# ProPrj_TPS__2025-07-25.net
KiCad netlist of a schematic drawn in EasyEDA Pro
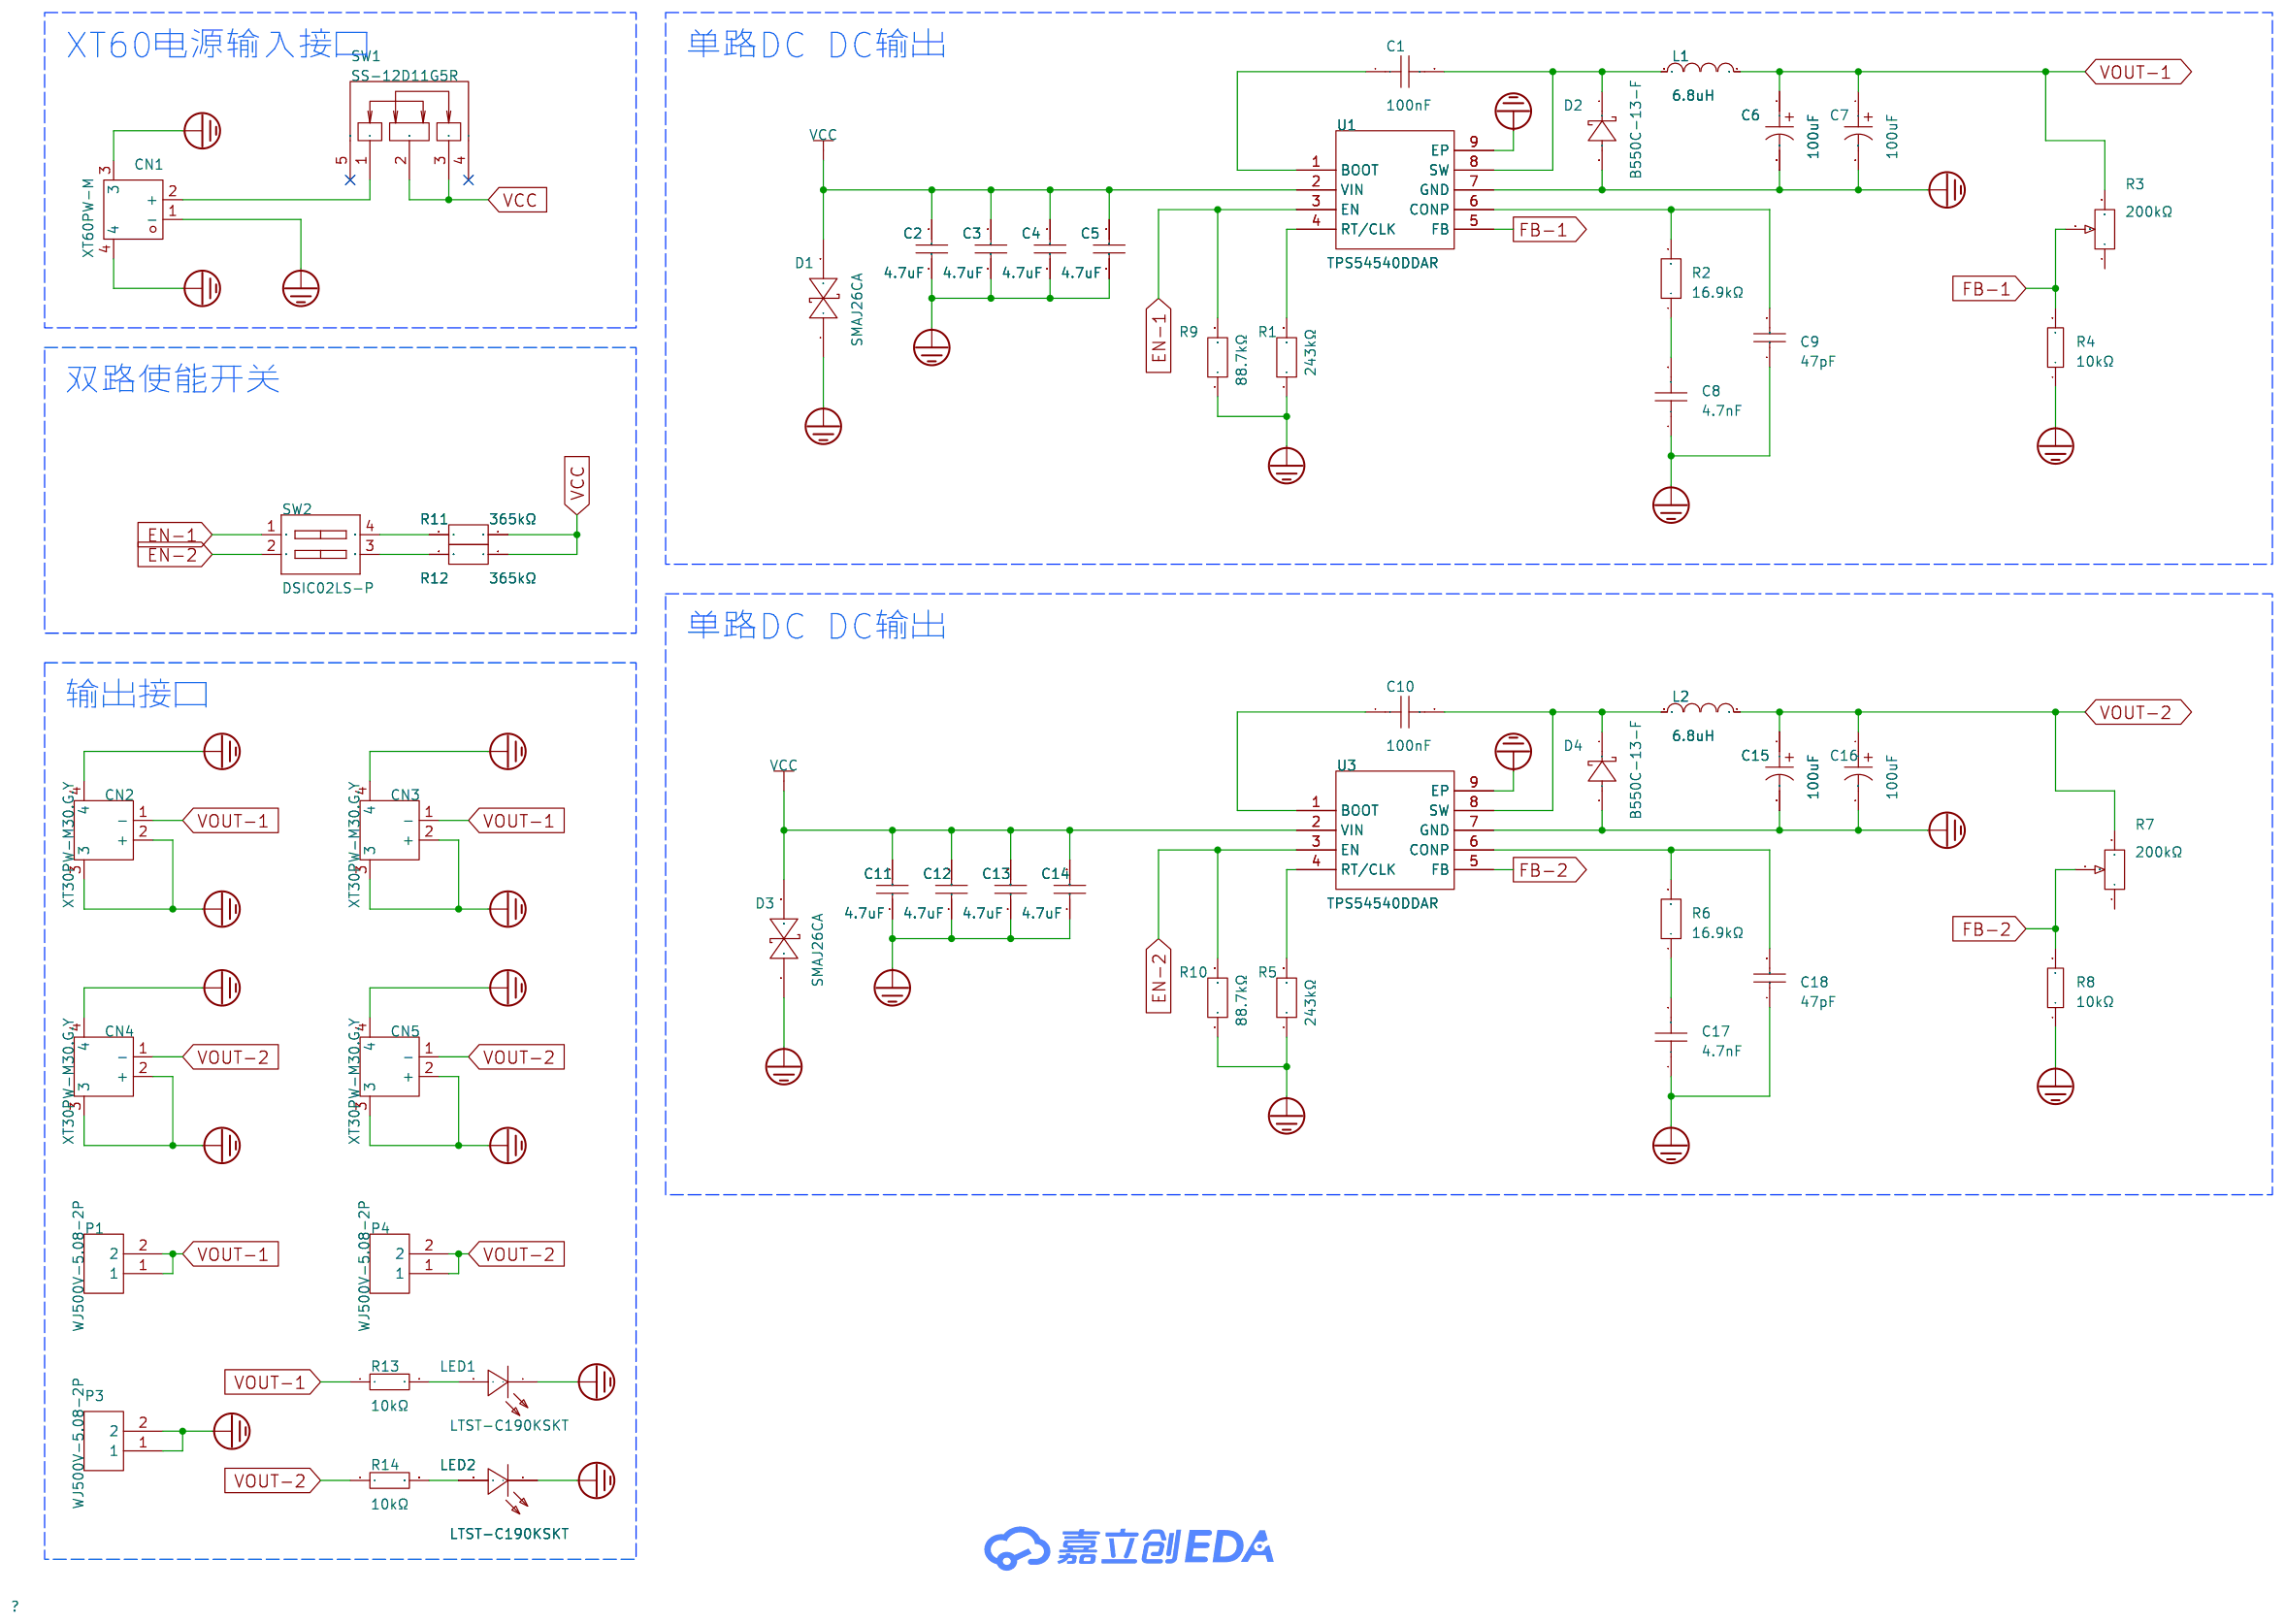
[diagram p0: schematic sheet]

(export (version "E")
  (design (tool "Eeschema 10.0.6"))
  (components
    (comp (ref "C1")
      (value "100nF")
      (footprint "easyedapro:C0603")
      (description "容值:100nF;精度:±10%;额定电压:50V;温度系数:X7R;")
      (fields
        (field (name "Manufacturer Part") "CGA0603X7R104K500JT")
        (field (name "Manufacturer") "HRE(芯声)")
      )
      (libsource (lib "easyedapro") (part "CGA0603X7R104K500JT"))
    )
    (comp (ref "C2")
      (value "4.7uF")
      (footprint "easyedapro:C0805")
      (description "容值:4.7uF;精度:±10%;额定电压:50V;材质(温度系数):X5R;")
      (fields
        (field (name "Manufacturer Part") "CL21A475KBQNNNE")
        (field (name "Manufacturer") "SAMSUNG(三星)")
      )
      (libsource (lib "easyedapro") (part "CL21A475KBQNNNE"))
    )
    (comp (ref "C3")
      (value "4.7uF")
      (footprint "easyedapro:C0805")
      (description "容值:4.7uF;精度:±10%;额定电压:50V;材质(温度系数):X5R;")
      (fields
        (field (name "Manufacturer Part") "CL21A475KBQNNNE")
        (field (name "Manufacturer") "SAMSUNG(三星)")
      )
      (libsource (lib "easyedapro") (part "CL21A475KBQNNNE"))
    )
    (comp (ref "C4")
      (value "4.7uF")
      (footprint "easyedapro:C0805")
      (description "容值:4.7uF;精度:±10%;额定电压:50V;材质(温度系数):X5R;")
      (fields
        (field (name "Manufacturer Part") "CL21A475KBQNNNE")
        (field (name "Manufacturer") "SAMSUNG(三星)")
      )
      (libsource (lib "easyedapro") (part "CL21A475KBQNNNE"))
    )
    (comp (ref "C5")
      (value "4.7uF")
      (footprint "easyedapro:C0805")
      (description "容值:4.7uF;精度:±10%;额定电压:50V;材质(温度系数):X5R;")
      (fields
        (field (name "Manufacturer Part") "CL21A475KBQNNNE")
        (field (name "Manufacturer") "SAMSUNG(三星)")
      )
      (libsource (lib "easyedapro") (part "CL21A475KBQNNNE"))
    )
    (comp (ref "C6")
      (value "100uF")
      (footprint "easyedapro:CAP-TH_BD8.0-P3.50-D0.6-FD")
      (description "容值:100uF;精度:±20%;额定电压:50V;纹波电流:2.9A@100kHz;等效串联电阻(ESR):30mΩ@100kHz;类型:聚合物;")
      (fields (field (name "Manufacturer Part") "PA50V100M8x8") (field (name "Manufacturer") "捷而瑞"))
      (libsource (lib "easyedapro") (part "PA50V100M8X8"))
    )
    (comp (ref "C7")
      (value "100uF")
      (footprint "easyedapro:CAP-TH_BD8.0-P3.50-D0.6-FD")
      (description "容值:100uF;精度:±20%;额定电压:50V;纹波电流:2.9A@100kHz;等效串联电阻(ESR):30mΩ@100kHz;类型:聚合物;")
      (fields (field (name "Manufacturer Part") "PA50V100M8x8") (field (name "Manufacturer") "捷而瑞"))
      (libsource (lib "easyedapro") (part "PA50V100M8X8"))
    )
    (comp (ref "C8")
      (value "4.7nF")
      (footprint "easyedapro:C0603")
      (description "容值:4.7nF;精度:±10%;额定电压:50V;温度系数:X7R;")
      (fields
        (field (name "Manufacturer Part") "CGA0603X7R472K500JT")
        (field (name "Manufacturer") "HRE(芯声)")
      )
      (libsource (lib "easyedapro") (part "CGA0603X7R472K500JT"))
    )
    (comp (ref "C9")
      (value "47pF")
      (footprint "easyedapro:C0603")
      (description "容值:47pF;精度:±5%;额定电压:50V;材质(温度系数):C0G;")
      (fields
        (field (name "Manufacturer Part") "CL10C470JB8NNNC")
        (field (name "Manufacturer") "SAMSUNG(三星)")
      )
      (libsource (lib "easyedapro") (part "CL10C470JB8NNNC"))
    )
    (comp (ref "C10")
      (value "100nF")
      (footprint "easyedapro:C0603")
      (description "容值:100nF;精度:±10%;额定电压:50V;温度系数:X7R;")
      (fields
        (field (name "Manufacturer Part") "CGA0603X7R104K500JT")
        (field (name "Manufacturer") "HRE(芯声)")
      )
      (libsource (lib "easyedapro") (part "CGA0603X7R104K500JT"))
    )
    (comp (ref "C11")
      (value "4.7uF")
      (footprint "easyedapro:C0805")
      (description "容值:4.7uF;精度:±10%;额定电压:50V;材质(温度系数):X5R;")
      (fields
        (field (name "Manufacturer Part") "CL21A475KBQNNNE")
        (field (name "Manufacturer") "SAMSUNG(三星)")
      )
      (libsource (lib "easyedapro") (part "CL21A475KBQNNNE"))
    )
    (comp (ref "C12")
      (value "4.7uF")
      (footprint "easyedapro:C0805")
      (description "容值:4.7uF;精度:±10%;额定电压:50V;材质(温度系数):X5R;")
      (fields
        (field (name "Manufacturer Part") "CL21A475KBQNNNE")
        (field (name "Manufacturer") "SAMSUNG(三星)")
      )
      (libsource (lib "easyedapro") (part "CL21A475KBQNNNE"))
    )
    (comp (ref "C13")
      (value "4.7uF")
      (footprint "easyedapro:C0805")
      (description "容值:4.7uF;精度:±10%;额定电压:50V;材质(温度系数):X5R;")
      (fields
        (field (name "Manufacturer Part") "CL21A475KBQNNNE")
        (field (name "Manufacturer") "SAMSUNG(三星)")
      )
      (libsource (lib "easyedapro") (part "CL21A475KBQNNNE"))
    )
    (comp (ref "C14")
      (value "4.7uF")
      (footprint "easyedapro:C0805")
      (description "容值:4.7uF;精度:±10%;额定电压:50V;材质(温度系数):X5R;")
      (fields
        (field (name "Manufacturer Part") "CL21A475KBQNNNE")
        (field (name "Manufacturer") "SAMSUNG(三星)")
      )
      (libsource (lib "easyedapro") (part "CL21A475KBQNNNE"))
    )
    (comp (ref "C15")
      (value "100uF")
      (footprint "easyedapro:CAP-TH_BD8.0-P3.50-D0.6-FD")
      (description "容值:100uF;精度:±20%;额定电压:50V;纹波电流:2.9A@100kHz;等效串联电阻(ESR):30mΩ@100kHz;类型:聚合物;")
      (fields (field (name "Manufacturer Part") "PA50V100M8x8") (field (name "Manufacturer") "捷而瑞"))
      (libsource (lib "easyedapro") (part "PA50V100M8X8"))
    )
    (comp (ref "C16")
      (value "100uF")
      (footprint "easyedapro:CAP-TH_BD8.0-P3.50-D0.6-FD")
      (description "容值:100uF;精度:±20%;额定电压:50V;纹波电流:2.9A@100kHz;等效串联电阻(ESR):30mΩ@100kHz;类型:聚合物;")
      (fields (field (name "Manufacturer Part") "PA50V100M8x8") (field (name "Manufacturer") "捷而瑞"))
      (libsource (lib "easyedapro") (part "PA50V100M8X8"))
    )
    (comp (ref "C17")
      (value "4.7nF")
      (footprint "easyedapro:C0603")
      (description "容值:4.7nF;精度:±10%;额定电压:50V;温度系数:X7R;")
      (fields
        (field (name "Manufacturer Part") "CGA0603X7R472K500JT")
        (field (name "Manufacturer") "HRE(芯声)")
      )
      (libsource (lib "easyedapro") (part "CGA0603X7R472K500JT"))
    )
    (comp (ref "C18")
      (value "47pF")
      (footprint "easyedapro:C0603")
      (description "容值:47pF;精度:±5%;额定电压:50V;材质(温度系数):C0G;")
      (fields
        (field (name "Manufacturer Part") "CL10C470JB8NNNC")
        (field (name "Manufacturer") "SAMSUNG(三星)")
      )
      (libsource (lib "easyedapro") (part "CL10C470JB8NNNC"))
    )
    (comp (ref "CN1")
      (value "XT60PW-M")
      (footprint "easyedapro:CONN-TH_XT60PW-M")
      (description "类别:-;类型1:-;")
      (fields (field (name "Manufacturer") "AMASS(艾迈斯)"))
      (libsource (lib "easyedapro") (part "XT60PW-M"))
    )
    (comp (ref "CN2")
      (value "XT30PW-M30.G.Y")
      (footprint "easyedapro:CONN-TH_XT30PW-M")
      (description "类别:-;类型1:-;")
      (fields (field (name "Manufacturer") "AMASS(艾迈斯)"))
      (libsource (lib "easyedapro") (part "XT30PW-M"))
    )
    (comp (ref "CN3")
      (value "XT30PW-M30.G.Y")
      (footprint "easyedapro:CONN-TH_XT30PW-M")
      (description "类别:-;类型1:-;")
      (fields (field (name "Manufacturer") "AMASS(艾迈斯)"))
      (libsource (lib "easyedapro") (part "XT30PW-M"))
    )
    (comp (ref "CN4")
      (value "XT30PW-M30.G.Y")
      (footprint "easyedapro:CONN-TH_XT30PW-M")
      (description "类别:-;类型1:-;")
      (fields (field (name "Manufacturer") "AMASS(艾迈斯)"))
      (libsource (lib "easyedapro") (part "XT30PW-M"))
    )
    (comp (ref "CN5")
      (value "XT30PW-M30.G.Y")
      (footprint "easyedapro:CONN-TH_XT30PW-M")
      (description "类别:-;类型1:-;")
      (fields (field (name "Manufacturer") "AMASS(艾迈斯)"))
      (libsource (lib "easyedapro") (part "XT30PW-M"))
    )
    (comp (ref "D1")
      (value "SMAJ26CA")
      (footprint "easyedapro:SMA_L4.4-W2.6-LS5.0-BI")
      (description "反向截止电压(Vrwm):26V;最大钳位电压:42.1V;峰值脉冲电流(Ipp)@10/1000us:9.5A;击穿电压:28.9V;")
      (fields (field (name "Manufacturer") "MDD"))
      (libsource (lib "easyedapro") (part "SMAJ26CA_C173517"))
    )
    (comp (ref "D2")
      (value "B550C-13-F")
      (footprint "easyedapro:SMC_L6.9-W5.9-LS7.9-RD")
      (description "二极管配置:-;正向压降(Vf):575mV@5A;直流反向耐压(Vr):50V;整流电流:5A;")
      (fields (field (name "Manufacturer") "DIODES(美台)"))
      (libsource (lib "easyedapro") (part "B550C-13-F"))
    )
    (comp (ref "D3")
      (value "SMAJ26CA")
      (footprint "easyedapro:SMA_L4.4-W2.6-LS5.0-BI")
      (description "反向截止电压(Vrwm):26V;最大钳位电压:42.1V;峰值脉冲电流(Ipp)@10/1000us:9.5A;击穿电压:28.9V;")
      (fields (field (name "Manufacturer") "MDD"))
      (libsource (lib "easyedapro") (part "SMAJ26CA_C173517"))
    )
    (comp (ref "D4")
      (value "B550C-13-F")
      (footprint "easyedapro:SMC_L6.9-W5.9-LS7.9-RD")
      (description "二极管配置:-;正向压降(Vf):575mV@5A;直流反向耐压(Vr):50V;整流电流:5A;")
      (fields (field (name "Manufacturer") "DIODES(美台)"))
      (libsource (lib "easyedapro") (part "B550C-13-F"))
    )
    (comp (ref "L1")
      (value "6.8uH")
      (footprint "easyedapro:IND-SMD_L7.0-W6.6")
      (description "电感值:6.8uH;精度:±20%;额定电流:5A;饱和电流(Isat):6A;类型:一体成型电感;")
      (fields (field (name "Manufacturer Part") "FXL0630-6R8-M") (field (name "Manufacturer") "cjiang(长江微电)"))
      (libsource (lib "easyedapro") (part "FXL0630-6R8-M"))
    )
    (comp (ref "L2")
      (value "6.8uH")
      (footprint "easyedapro:IND-SMD_L7.0-W6.6")
      (description "电感值:6.8uH;精度:±20%;额定电流:5A;饱和电流(Isat):6A;类型:一体成型电感;")
      (fields (field (name "Manufacturer Part") "FXL0630-6R8-M") (field (name "Manufacturer") "cjiang(长江微电)"))
      (libsource (lib "easyedapro") (part "FXL0630-6R8-M"))
    )
    (comp (ref "LED1")
      (value "LTST-C190KSKT")
      (footprint "easyedapro:LED0603-RD")
      (fields (field (name "Manufacturer") "LITEON(光宝)"))
      (libsource (lib "easyedapro") (part "LTST-C190KSKT"))
    )
    (comp (ref "LED2")
      (value "LTST-C190KSKT")
      (footprint "easyedapro:LED0603-RD")
      (fields (field (name "Manufacturer") "LITEON(光宝)"))
      (libsource (lib "easyedapro") (part "LTST-C190KSKT"))
    )
    (comp (ref "P1")
      (value "WJ500V-5.08-2P")
      (footprint "easyedapro:CONN-TH_2P-P5.00_WJ500V-5.08-2P")
      (fields (field (name "Manufacturer") "KANGNEX(康奈克斯电气)"))
      (libsource (lib "easyedapro") (part "WJ500V-5.08-2P-14-00A"))
    )
    (comp (ref "P3")
      (value "WJ500V-5.08-2P")
      (footprint "easyedapro:CONN-TH_2P-P5.00_WJ500V-5.08-2P")
      (fields (field (name "Manufacturer") "KANGNEX(康奈克斯电气)"))
      (libsource (lib "easyedapro") (part "WJ500V-5.08-2P-14-00A"))
    )
    (comp (ref "P4")
      (value "WJ500V-5.08-2P")
      (footprint "easyedapro:CONN-TH_2P-P5.00_WJ500V-5.08-2P")
      (fields (field (name "Manufacturer") "KANGNEX(康奈克斯电气)"))
      (libsource (lib "easyedapro") (part "WJ500V-5.08-2P-14-00A"))
    )
    (comp (ref "R1")
      (value "243kΩ")
      (footprint "easyedapro:R0603")
      (description "电阻类型:薄膜电阻;阻值:243kΩ;精度:±0.1%;功率:100mW;温度系数:±25ppm/°C;")
      (fields (field (name "Manufacturer Part") "RT0603BRD07243KL") (field (name "Manufacturer") "YAGEO(国巨)"))
      (libsource (lib "easyedapro") (part "RT0603BRD07243KL"))
    )
    (comp (ref "R2")
      (value "16.9kΩ")
      (footprint "easyedapro:R0603")
      (description "电阻类型:薄膜电阻;阻值:16.9kΩ;精度:±0.1%;功率:100mW;温度系数:±25ppm/°C;")
      (fields (field (name "Manufacturer Part") "RT0603BRD0716K9L") (field (name "Manufacturer") "YAGEO(国巨)"))
      (libsource (lib "easyedapro") (part "RT0603BRD0716K9L"))
    )
    (comp (ref "R3")
      (value "200kΩ")
      (footprint "easyedapro:RES-ADJ-TH_3P-L7.1-W6.9-P2.50-L_3362P")
      (description "阻值:200kΩ;精度:±10%;")
      (fields (field (name "Manufacturer Part") "3362P-1-204") (field (name "Manufacturer") "BOCHEN(博晨)"))
      (libsource (lib "easyedapro") (part "3362P-1-204"))
    )
    (comp (ref "R4")
      (value "10kΩ")
      (footprint "easyedapro:R0603")
      (description "电阻类型:厚膜电阻;阻值:10kΩ;精度:±1%;功率:100mW;工作电压:75V;温度系数:±100ppm/°C;")
      (fields
        (field (name "Manufacturer Part") "0603WAF1002T5E")
        (field (name "Manufacturer") "UNI-ROYAL(厚声)")
      )
      (libsource (lib "easyedapro") (part "0603WAF1002T5E"))
    )
    (comp (ref "R5")
      (value "243kΩ")
      (footprint "easyedapro:R0603")
      (description "电阻类型:薄膜电阻;阻值:243kΩ;精度:±0.1%;功率:100mW;温度系数:±25ppm/°C;")
      (fields (field (name "Manufacturer Part") "RT0603BRD07243KL") (field (name "Manufacturer") "YAGEO(国巨)"))
      (libsource (lib "easyedapro") (part "RT0603BRD07243KL"))
    )
    (comp (ref "R6")
      (value "16.9kΩ")
      (footprint "easyedapro:R0603")
      (description "电阻类型:薄膜电阻;阻值:16.9kΩ;精度:±0.1%;功率:100mW;温度系数:±25ppm/°C;")
      (fields (field (name "Manufacturer Part") "RT0603BRD0716K9L") (field (name "Manufacturer") "YAGEO(国巨)"))
      (libsource (lib "easyedapro") (part "RT0603BRD0716K9L"))
    )
    (comp (ref "R7")
      (value "200kΩ")
      (footprint "easyedapro:RES-ADJ-TH_3P-L7.1-W6.9-P2.50-L_3362P")
      (description "阻值:200kΩ;精度:±10%;")
      (fields (field (name "Manufacturer Part") "3362P-1-204") (field (name "Manufacturer") "BOCHEN(博晨)"))
      (libsource (lib "easyedapro") (part "3362P-1-204"))
    )
    (comp (ref "R8")
      (value "10kΩ")
      (footprint "easyedapro:R0603")
      (description "电阻类型:厚膜电阻;阻值:10kΩ;精度:±1%;功率:100mW;工作电压:75V;温度系数:±100ppm/°C;")
      (fields
        (field (name "Manufacturer Part") "0603WAF1002T5E")
        (field (name "Manufacturer") "UNI-ROYAL(厚声)")
      )
      (libsource (lib "easyedapro") (part "0603WAF1002T5E"))
    )
    (comp (ref "R9")
      (value "88.7kΩ")
      (footprint "easyedapro:R0603")
      (description "电阻类型:厚膜电阻;阻值:88.7kΩ;精度:±1%;功率:100mW;最大工作电压:75V;温度系数:±100ppm/°C;")
      (fields (field (name "Manufacturer Part") "FRC0603F8872TS") (field (name "Manufacturer") "FOJAN(富捷)"))
      (libsource (lib "easyedapro") (part "FRC0603F8872TS"))
    )
    (comp (ref "R10")
      (value "88.7kΩ")
      (footprint "easyedapro:R0603")
      (description "电阻类型:厚膜电阻;阻值:88.7kΩ;精度:±1%;功率:100mW;最大工作电压:75V;温度系数:±100ppm/°C;")
      (fields (field (name "Manufacturer Part") "FRC0603F8872TS") (field (name "Manufacturer") "FOJAN(富捷)"))
      (libsource (lib "easyedapro") (part "FRC0603F8872TS"))
    )
    (comp (ref "R11")
      (value "365kΩ")
      (footprint "easyedapro:R0603")
      (description "电阻类型:薄膜电阻;阻值:365kΩ;精度:±0.1%;功率:100mW;最大工作电压:75V;温度系数:±50ppm/°C;")
      (fields (field (name "Manufacturer Part") "RT0603BRE07365KL") (field (name "Manufacturer") "YAGEO(国巨)"))
      (libsource (lib "easyedapro") (part "RT0603BRE07365KL"))
    )
    (comp (ref "R12")
      (value "365kΩ")
      (footprint "easyedapro:R0603")
      (description "电阻类型:薄膜电阻;阻值:365kΩ;精度:±0.1%;功率:100mW;最大工作电压:75V;温度系数:±50ppm/°C;")
      (fields (field (name "Manufacturer Part") "RT0603BRE07365KL") (field (name "Manufacturer") "YAGEO(国巨)"))
      (libsource (lib "easyedapro") (part "RT0603BRE07365KL"))
    )
    (comp (ref "R13")
      (value "10kΩ")
      (footprint "easyedapro:R0603")
      (description "电阻类型:厚膜电阻;阻值:10kΩ;精度:±1%;功率:100mW;工作电压:75V;温度系数:±100ppm/°C;")
      (fields
        (field (name "Manufacturer Part") "0603WAF1002T5E")
        (field (name "Manufacturer") "UNI-ROYAL(厚声)")
      )
      (libsource (lib "easyedapro") (part "0603WAF1002T5E"))
    )
    (comp (ref "R14")
      (value "10kΩ")
      (footprint "easyedapro:R0603")
      (description "电阻类型:厚膜电阻;阻值:10kΩ;精度:±1%;功率:100mW;工作电压:75V;温度系数:±100ppm/°C;")
      (fields
        (field (name "Manufacturer Part") "0603WAF1002T5E")
        (field (name "Manufacturer") "UNI-ROYAL(厚声)")
      )
      (libsource (lib "easyedapro") (part "0603WAF1002T5E"))
    )
    (comp (ref "SW1")
      (value "SS-12D11G5R")
      (footprint "easyedapro:SW-TH_SS-12D11G5R")
      (description "电路结构:单刀双掷;安装方式:弯插;开关颜色:黑色;额定电流(DC):5A;额定电压(DC):125V;额定电流(AC):5A;额定电压(AC):125V;机械寿命:1万次;")
      (fields (field (name "Manufacturer") "XKB Connectivity(中国星坤)"))
      (libsource (lib "easyedapro") (part "SS-12D11G5R"))
    )
    (comp (ref "SW2")
      (value "DSIC02LS-P")
      (footprint "easyedapro:SW-SMD_4P-L5.1-W6.1-P2.54-LS9.8")
      (description "类型:平拨,凸起式;电路结构:单刀单掷;开关位数:2位;额定电流:25mA;额定电压:24V;使用寿命:3千次;颜色:黑色;")
      (fields (field (name "Manufacturer") "XKB Connectivity(中国星坤)"))
      (libsource (lib "easyedapro") (part "DSIC02LS-P_C489174"))
    )
    (comp (ref "U1")
      (value "TPS54540DDAR")
      (footprint "easyedapro:SOIC-8_L4.9-W3.9-P1.27-LS6.0-BL-EP")
      (description "功能类型:降压型;输出类型:可调;工作电压:4.5V~42V;输出电压:800mV~41.1V;输出电流:5A;")
      (fields (field (name "Manufacturer") "TI(德州仪器)"))
      (libsource (lib "easyedapro") (part "TPS54540DDAR"))
    )
    (comp (ref "U3")
      (value "TPS54540DDAR")
      (footprint "easyedapro:SOIC-8_L4.9-W3.9-P1.27-LS6.0-BL-EP")
      (description "功能类型:降压型;输出类型:可调;工作电压:4.5V~42V;输出电压:800mV~41.1V;输出电流:5A;")
      (fields (field (name "Manufacturer") "TI(德州仪器)"))
      (libsource (lib "easyedapro") (part "TPS54540DDAR"))
    )
  )
  (nets
    (net (code "1") (name "EN-1") (class "Default")
      (node (ref "R9") (pin "2") (pinfunction "2_2") (pintype "unspecified"))
      (node (ref "SW2") (pin "1") (pinfunction "A1_1") (pintype "input"))
      (node (ref "U1") (pin "3") (pinfunction "EN_3") (pintype "unspecified"))
    )
    (net (code "2") (name "EN-2") (class "Default")
      (node (ref "R10") (pin "2") (pinfunction "2_2") (pintype "unspecified"))
      (node (ref "SW2") (pin "2") (pinfunction "A2_2") (pintype "input"))
      (node (ref "U3") (pin "3") (pinfunction "EN_3") (pintype "unspecified"))
    )
    (net (code "3") (name "FB-1") (class "Default")
      (node (ref "R3") (pin "2") (pinfunction "2_2") (pintype "input"))
      (node (ref "R4") (pin "2") (pinfunction "2_2") (pintype "input"))
      (node (ref "U1") (pin "5") (pinfunction "FB_5") (pintype "unspecified"))
    )
    (net (code "4") (name "FB-2") (class "Default")
      (node (ref "R7") (pin "2") (pinfunction "2_2") (pintype "input"))
      (node (ref "R8") (pin "2") (pinfunction "2_2") (pintype "input"))
      (node (ref "U3") (pin "5") (pinfunction "FB_5") (pintype "unspecified"))
    )
    (net (code "5") (name "Net-(C8-Pad2)") (class "Default")
      (node (ref "C8") (pin "2") (pinfunction "2_2") (pintype "unspecified"))
      (node (ref "R2") (pin "1") (pinfunction "1_1") (pintype "unspecified"))
    )
    (net (code "6") (name "Net-(C17-Pad2)") (class "Default")
      (node (ref "C17") (pin "2") (pinfunction "2_2") (pintype "unspecified"))
      (node (ref "R6") (pin "1") (pinfunction "1_1") (pintype "unspecified"))
    )
    (net (code "7") (name "Net-(CN1-+)") (class "Default")
      (node (ref "CN1") (pin "2") (pinfunction "+_2") (pintype "unspecified"))
      (node (ref "SW1") (pin "1") (pinfunction "1_1") (pintype "unspecified"))
    )
    (net (code "8") (name "Net-(D2-C)") (class "Default")
      (node (ref "C1") (pin "2") (pinfunction "2_2") (pintype "unspecified"))
      (node (ref "D2") (pin "1") (pinfunction "C_1") (pintype "unspecified"))
      (node (ref "L1") (pin "1") (pinfunction "1_1") (pintype "unspecified"))
      (node (ref "U1") (pin "8") (pinfunction "SW_8") (pintype "unspecified"))
    )
    (net (code "9") (name "Net-(D4-C)") (class "Default")
      (node (ref "C10") (pin "2") (pinfunction "2_2") (pintype "unspecified"))
      (node (ref "D4") (pin "1") (pinfunction "C_1") (pintype "unspecified"))
      (node (ref "L2") (pin "1") (pinfunction "1_1") (pintype "unspecified"))
      (node (ref "U3") (pin "8") (pinfunction "SW_8") (pintype "unspecified"))
    )
    (net (code "10") (name "Net-(LED1-+)") (class "Default")
      (node (ref "LED1") (pin "2") (pinfunction "+_2") (pintype "unspecified"))
      (node (ref "R13") (pin "2") (pinfunction "2_2") (pintype "input"))
    )
    (net (code "11") (name "Net-(LED2-+)") (class "Default")
      (node (ref "LED2") (pin "2") (pinfunction "+_2") (pintype "unspecified"))
      (node (ref "R14") (pin "2") (pinfunction "2_2") (pintype "input"))
    )
    (net (code "12") (name "Net-(SW2-B1)") (class "Default")
      (node (ref "R11") (pin "2") (pinfunction "2_2") (pintype "unspecified"))
      (node (ref "SW2") (pin "4") (pinfunction "B1_4") (pintype "input"))
    )
    (net (code "13") (name "Net-(SW2-B2)") (class "Default")
      (node (ref "R12") (pin "2") (pinfunction "2_2") (pintype "unspecified"))
      (node (ref "SW2") (pin "3") (pinfunction "B2_3") (pintype "input"))
    )
    (net (code "14") (name "Net-(U1-BOOT)") (class "Default")
      (node (ref "C1") (pin "1") (pinfunction "1_1") (pintype "unspecified"))
      (node (ref "U1") (pin "1") (pinfunction "BOOT_1") (pintype "unspecified"))
    )
    (net (code "15") (name "Net-(U1-CONP)") (class "Default")
      (node (ref "C9") (pin "2") (pinfunction "2_2") (pintype "input"))
      (node (ref "R2") (pin "2") (pinfunction "2_2") (pintype "unspecified"))
      (node (ref "U1") (pin "6") (pinfunction "CONP_6") (pintype "unspecified"))
    )
    (net (code "16") (name "Net-(U1-RT{slash}CLK)") (class "Default")
      (node (ref "R1") (pin "2") (pinfunction "2_2") (pintype "unspecified"))
      (node (ref "U1") (pin "4") (pinfunction "RT/CLK_4") (pintype "unspecified"))
    )
    (net (code "17") (name "Net-(U3-BOOT)") (class "Default")
      (node (ref "C10") (pin "1") (pinfunction "1_1") (pintype "unspecified"))
      (node (ref "U3") (pin "1") (pinfunction "BOOT_1") (pintype "unspecified"))
    )
    (net (code "18") (name "Net-(U3-CONP)") (class "Default")
      (node (ref "C18") (pin "2") (pinfunction "2_2") (pintype "input"))
      (node (ref "R6") (pin "2") (pinfunction "2_2") (pintype "unspecified"))
      (node (ref "U3") (pin "6") (pinfunction "CONP_6") (pintype "unspecified"))
    )
    (net (code "19") (name "Net-(U3-RT{slash}CLK)") (class "Default")
      (node (ref "R5") (pin "2") (pinfunction "2_2") (pintype "unspecified"))
      (node (ref "U3") (pin "4") (pinfunction "RT/CLK_4") (pintype "unspecified"))
    )
    (net (code "20") (name "PGND") (class "Default")
      (node (ref "C11") (pin "1") (pinfunction "1_1") (pintype "input"))
      (node (ref "C12") (pin "1") (pinfunction "1_1") (pintype "input"))
      (node (ref "C13") (pin "1") (pinfunction "1_1") (pintype "input"))
      (node (ref "C14") (pin "1") (pinfunction "1_1") (pintype "input"))
      (node (ref "C15") (pin "2") (pinfunction "2_2") (pintype "input"))
      (node (ref "C16") (pin "2") (pinfunction "2_2") (pintype "input"))
      (node (ref "C17") (pin "1") (pinfunction "1_1") (pintype "unspecified"))
      (node (ref "C18") (pin "1") (pinfunction "1_1") (pintype "input"))
      (node (ref "C2") (pin "1") (pinfunction "1_1") (pintype "input"))
      (node (ref "C3") (pin "1") (pinfunction "1_1") (pintype "input"))
      (node (ref "C4") (pin "1") (pinfunction "1_1") (pintype "input"))
      (node (ref "C5") (pin "1") (pinfunction "1_1") (pintype "input"))
      (node (ref "C6") (pin "2") (pinfunction "2_2") (pintype "input"))
      (node (ref "C7") (pin "2") (pinfunction "2_2") (pintype "input"))
      (node (ref "C8") (pin "1") (pinfunction "1_1") (pintype "unspecified"))
      (node (ref "C9") (pin "1") (pinfunction "1_1") (pintype "input"))
      (node (ref "CN1") (pin "1") (pinfunction "-_1") (pintype "unspecified"))
      (node (ref "CN1") (pin "3") (pinfunction "3_3") (pintype "unspecified"))
      (node (ref "CN1") (pin "4") (pinfunction "4_4") (pintype "unspecified"))
      (node (ref "CN2") (pin "2") (pinfunction "+_2") (pintype "unspecified"))
      (node (ref "CN2") (pin "3") (pinfunction "3_3") (pintype "unspecified"))
      (node (ref "CN2") (pin "4") (pinfunction "4_4") (pintype "unspecified"))
      (node (ref "CN3") (pin "2") (pinfunction "+_2") (pintype "unspecified"))
      (node (ref "CN3") (pin "3") (pinfunction "3_3") (pintype "unspecified"))
      (node (ref "CN3") (pin "4") (pinfunction "4_4") (pintype "unspecified"))
      (node (ref "CN4") (pin "2") (pinfunction "+_2") (pintype "unspecified"))
      (node (ref "CN4") (pin "3") (pinfunction "3_3") (pintype "unspecified"))
      (node (ref "CN4") (pin "4") (pinfunction "4_4") (pintype "unspecified"))
      (node (ref "CN5") (pin "2") (pinfunction "+_2") (pintype "unspecified"))
      (node (ref "CN5") (pin "3") (pinfunction "3_3") (pintype "unspecified"))
      (node (ref "CN5") (pin "4") (pinfunction "4_4") (pintype "unspecified"))
      (node (ref "D1") (pin "1") (pinfunction "1_1") (pintype "unspecified"))
      (node (ref "D2") (pin "2") (pinfunction "A_2") (pintype "unspecified"))
      (node (ref "D3") (pin "1") (pinfunction "1_1") (pintype "unspecified"))
      (node (ref "D4") (pin "2") (pinfunction "A_2") (pintype "unspecified"))
      (node (ref "LED1") (pin "1") (pinfunction "-_1") (pintype "unspecified"))
      (node (ref "LED2") (pin "1") (pinfunction "-_1") (pintype "unspecified"))
      (node (ref "P3") (pin "1") (pinfunction "1_1") (pintype "unspecified"))
      (node (ref "P3") (pin "2") (pinfunction "2_2") (pintype "unspecified"))
      (node (ref "R1") (pin "1") (pinfunction "1_1") (pintype "unspecified"))
      (node (ref "R10") (pin "1") (pinfunction "1_1") (pintype "unspecified"))
      (node (ref "R4") (pin "1") (pinfunction "1_1") (pintype "input"))
      (node (ref "R5") (pin "1") (pinfunction "1_1") (pintype "unspecified"))
      (node (ref "R8") (pin "1") (pinfunction "1_1") (pintype "input"))
      (node (ref "R9") (pin "1") (pinfunction "1_1") (pintype "unspecified"))
      (node (ref "U1") (pin "7") (pinfunction "GND_7") (pintype "unspecified"))
      (node (ref "U1") (pin "9") (pinfunction "EP_9") (pintype "unspecified"))
      (node (ref "U3") (pin "7") (pinfunction "GND_7") (pintype "unspecified"))
      (node (ref "U3") (pin "9") (pinfunction "EP_9") (pintype "unspecified"))
    )
    (net (code "21") (name "VCC") (class "Default")
      (node (ref "C11") (pin "2") (pinfunction "2_2") (pintype "input"))
      (node (ref "C12") (pin "2") (pinfunction "2_2") (pintype "input"))
      (node (ref "C13") (pin "2") (pinfunction "2_2") (pintype "input"))
      (node (ref "C14") (pin "2") (pinfunction "2_2") (pintype "input"))
      (node (ref "C2") (pin "2") (pinfunction "2_2") (pintype "input"))
      (node (ref "C3") (pin "2") (pinfunction "2_2") (pintype "input"))
      (node (ref "C4") (pin "2") (pinfunction "2_2") (pintype "input"))
      (node (ref "C5") (pin "2") (pinfunction "2_2") (pintype "input"))
      (node (ref "D1") (pin "2") (pinfunction "2_2") (pintype "unspecified"))
      (node (ref "D3") (pin "2") (pinfunction "2_2") (pintype "unspecified"))
      (node (ref "R11") (pin "1") (pinfunction "1_1") (pintype "unspecified"))
      (node (ref "R12") (pin "1") (pinfunction "1_1") (pintype "unspecified"))
      (node (ref "SW1") (pin "2") (pinfunction "2_2") (pintype "unspecified"))
      (node (ref "SW1") (pin "3") (pinfunction "3_3") (pintype "unspecified"))
      (node (ref "U1") (pin "2") (pinfunction "VIN_2") (pintype "unspecified"))
      (node (ref "U3") (pin "2") (pinfunction "VIN_2") (pintype "unspecified"))
    )
    (net (code "22") (name "VOUT-1") (class "Default")
      (node (ref "C6") (pin "1") (pinfunction "1_1") (pintype "input"))
      (node (ref "C7") (pin "1") (pinfunction "1_1") (pintype "input"))
      (node (ref "CN2") (pin "1") (pinfunction "-_1") (pintype "unspecified"))
      (node (ref "CN3") (pin "1") (pinfunction "-_1") (pintype "unspecified"))
      (node (ref "L1") (pin "2") (pinfunction "2_2") (pintype "unspecified"))
      (node (ref "P1") (pin "1") (pinfunction "1_1") (pintype "unspecified"))
      (node (ref "P1") (pin "2") (pinfunction "2_2") (pintype "unspecified"))
      (node (ref "R13") (pin "1") (pinfunction "1_1") (pintype "input"))
      (node (ref "R3") (pin "3") (pinfunction "3_3") (pintype "input"))
    )
    (net (code "23") (name "VOUT-2") (class "Default")
      (node (ref "C15") (pin "1") (pinfunction "1_1") (pintype "input"))
      (node (ref "C16") (pin "1") (pinfunction "1_1") (pintype "input"))
      (node (ref "CN4") (pin "1") (pinfunction "-_1") (pintype "unspecified"))
      (node (ref "CN5") (pin "1") (pinfunction "-_1") (pintype "unspecified"))
      (node (ref "L2") (pin "2") (pinfunction "2_2") (pintype "unspecified"))
      (node (ref "P4") (pin "1") (pinfunction "1_1") (pintype "unspecified"))
      (node (ref "P4") (pin "2") (pinfunction "2_2") (pintype "unspecified"))
      (node (ref "R14") (pin "1") (pinfunction "1_1") (pintype "input"))
      (node (ref "R7") (pin "3") (pinfunction "3_3") (pintype "input"))
    )
    (net (code "24") (name "unconnected-(R3-Pad1)") (class "Default")
      (node (ref "R3") (pin "1") (pinfunction "1_1") (pintype "input"))
    )
    (net (code "25") (name "unconnected-(R7-Pad1)") (class "Default")
      (node (ref "R7") (pin "1") (pinfunction "1_1") (pintype "input"))
    )
    (net (code "26") (name "unconnected-(SW1-Pad4)") (class "Default")
      (node (ref "SW1") (pin "4") (pinfunction "4_4") (pintype "unspecified+no_connect"))
    )
    (net (code "27") (name "unconnected-(SW1-Pad5)") (class "Default")
      (node (ref "SW1") (pin "5") (pinfunction "5_5") (pintype "unspecified+no_connect"))
    )
  )
)
